# QO100_control.net
KiCad netlist of a schematic drawn in EAGLE
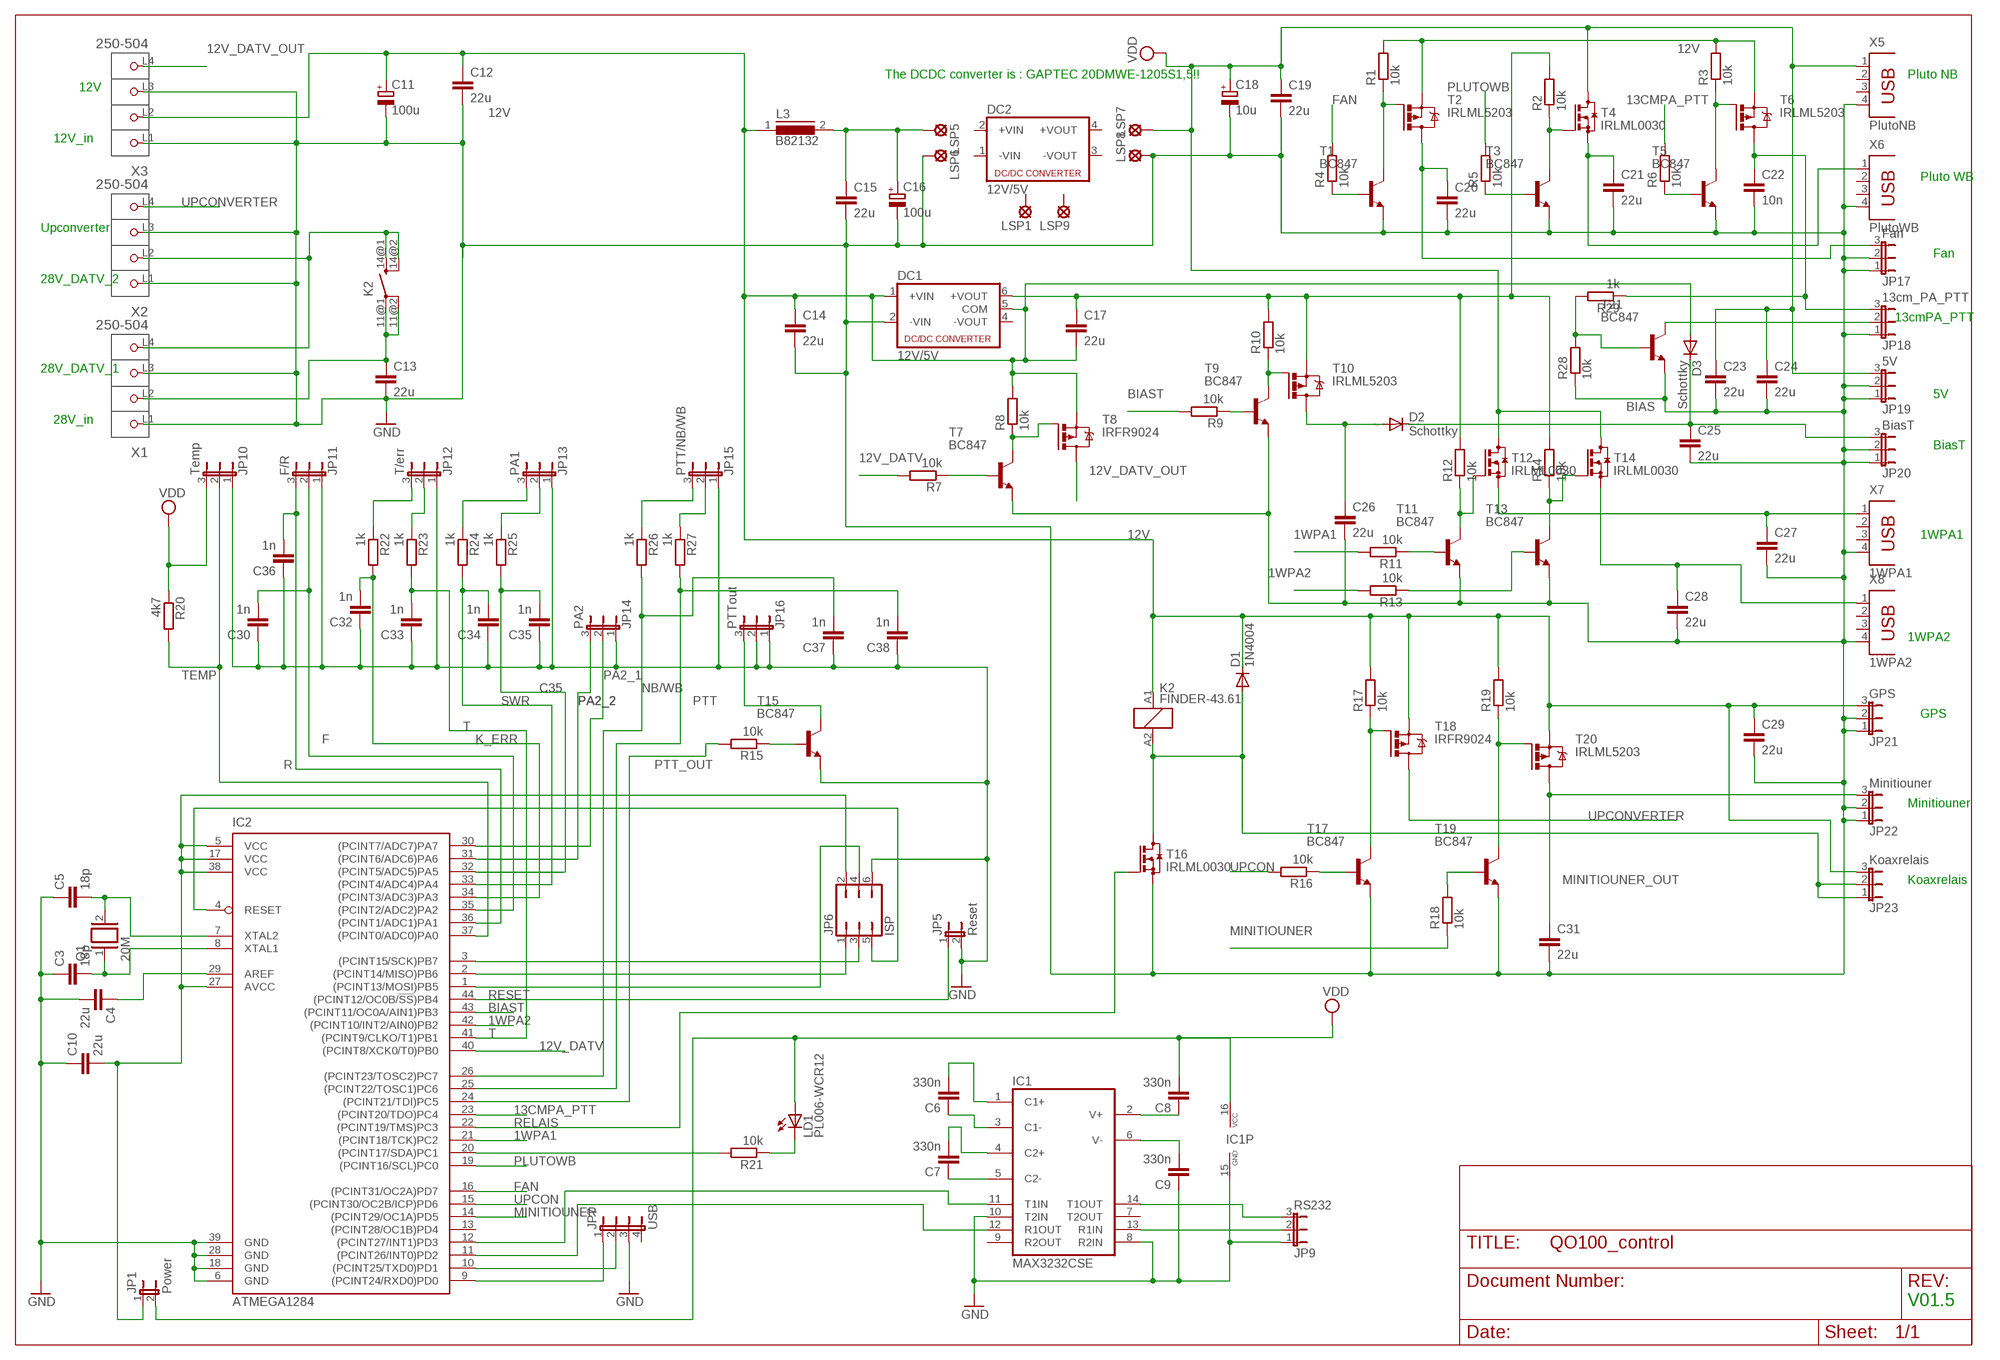
[diagram p0: schematic, sheet 1]

(export (version "E")
  (design (tool "Eeschema 10.0.6"))
  (components
    (comp (ref "C3")
      (value "18p")
      (footprint "eagle-import:C025-025X050")
      (libsource (lib "eagle-import") (part "C-EU025-025X050"))
    )
    (comp (ref "C4")
      (value "22u")
      (footprint "eagle-import:C1206")
      (libsource (lib "eagle-import") (part "resistor_C-EUC1206"))
    )
    (comp (ref "C5")
      (value "18p")
      (footprint "eagle-import:C025-025X050")
      (libsource (lib "eagle-import") (part "C-EU025-025X050"))
    )
    (comp (ref "C6")
      (value "330n")
      (footprint "eagle-import:C1206")
      (libsource (lib "eagle-import") (part "resistor_C-EUC1206"))
    )
    (comp (ref "C7")
      (value "330n")
      (footprint "eagle-import:C1206")
      (libsource (lib "eagle-import") (part "resistor_C-EUC1206"))
    )
    (comp (ref "C8")
      (value "330n")
      (footprint "eagle-import:C1206")
      (libsource (lib "eagle-import") (part "resistor_C-EUC1206"))
    )
    (comp (ref "C9")
      (value "330n")
      (footprint "eagle-import:C1206")
      (libsource (lib "eagle-import") (part "resistor_C-EUC1206"))
    )
    (comp (ref "C10")
      (value "22u")
      (footprint "eagle-import:C1206")
      (libsource (lib "eagle-import") (part "resistor_C-EUC1206"))
    )
    (comp (ref "C11")
      (value "100u")
      (footprint "eagle-import:E5-6")
      (libsource (lib "eagle-import") (part "CPOL-EUE5-6"))
    )
    (comp (ref "C12")
      (value "22u")
      (footprint "eagle-import:C1206")
      (libsource (lib "eagle-import") (part "resistor_C-EUC1206"))
    )
    (comp (ref "C13")
      (value "22u")
      (footprint "eagle-import:C1206")
      (libsource (lib "eagle-import") (part "resistor_C-EUC1206"))
    )
    (comp (ref "C14")
      (value "22u")
      (footprint "eagle-import:C1206")
      (libsource (lib "eagle-import") (part "resistor_C-EUC1206"))
    )
    (comp (ref "C15")
      (value "22u")
      (footprint "eagle-import:C1206")
      (libsource (lib "eagle-import") (part "resistor_C-EUC1206"))
    )
    (comp (ref "C16")
      (value "100u")
      (footprint "eagle-import:E5-6")
      (libsource (lib "eagle-import") (part "CPOL-EUE5-6"))
    )
    (comp (ref "C17")
      (value "22u")
      (footprint "eagle-import:C1206")
      (libsource (lib "eagle-import") (part "resistor_C-EUC1206"))
    )
    (comp (ref "C18")
      (value "10u")
      (footprint "eagle-import:E5-6")
      (libsource (lib "eagle-import") (part "CPOL-EUE5-6"))
    )
    (comp (ref "C19")
      (value "22u")
      (footprint "eagle-import:C1206")
      (libsource (lib "eagle-import") (part "resistor_C-EUC1206"))
    )
    (comp (ref "C20")
      (value "22u")
      (footprint "eagle-import:C1206")
      (libsource (lib "eagle-import") (part "resistor_C-EUC1206"))
    )
    (comp (ref "C21")
      (value "22u")
      (footprint "eagle-import:C1206")
      (libsource (lib "eagle-import") (part "resistor_C-EUC1206"))
    )
    (comp (ref "C22")
      (value "10n")
      (footprint "eagle-import:C1206")
      (libsource (lib "eagle-import") (part "resistor_C-EUC1206"))
    )
    (comp (ref "C23")
      (value "22u")
      (footprint "eagle-import:C1206")
      (libsource (lib "eagle-import") (part "resistor_C-EUC1206"))
    )
    (comp (ref "C24")
      (value "22u")
      (footprint "eagle-import:C1206")
      (libsource (lib "eagle-import") (part "resistor_C-EUC1206"))
    )
    (comp (ref "C25")
      (value "22u")
      (footprint "eagle-import:C1206")
      (libsource (lib "eagle-import") (part "resistor_C-EUC1206"))
    )
    (comp (ref "C26")
      (value "22u")
      (footprint "eagle-import:C1206")
      (libsource (lib "eagle-import") (part "resistor_C-EUC1206"))
    )
    (comp (ref "C27")
      (value "22u")
      (footprint "eagle-import:C1206")
      (libsource (lib "eagle-import") (part "resistor_C-EUC1206"))
    )
    (comp (ref "C28")
      (value "22u")
      (footprint "eagle-import:C1206")
      (libsource (lib "eagle-import") (part "resistor_C-EUC1206"))
    )
    (comp (ref "C29")
      (value "22u")
      (footprint "eagle-import:C1206")
      (libsource (lib "eagle-import") (part "resistor_C-EUC1206"))
    )
    (comp (ref "C30")
      (value "1n")
      (footprint "eagle-import:C1206")
      (libsource (lib "eagle-import") (part "resistor_C-EUC1206"))
    )
    (comp (ref "C31")
      (value "22u")
      (footprint "eagle-import:C1206")
      (libsource (lib "eagle-import") (part "resistor_C-EUC1206"))
    )
    (comp (ref "C32")
      (value "1n")
      (footprint "eagle-import:C1206")
      (libsource (lib "eagle-import") (part "resistor_C-EUC1206"))
    )
    (comp (ref "C33")
      (value "1n")
      (footprint "eagle-import:C1206")
      (libsource (lib "eagle-import") (part "resistor_C-EUC1206"))
    )
    (comp (ref "C34")
      (value "1n")
      (footprint "eagle-import:C1206")
      (libsource (lib "eagle-import") (part "resistor_C-EUC1206"))
    )
    (comp (ref "C35")
      (value "1n")
      (footprint "eagle-import:C1206")
      (libsource (lib "eagle-import") (part "resistor_C-EUC1206"))
    )
    (comp (ref "C36")
      (value "1n")
      (footprint "eagle-import:C1206")
      (libsource (lib "eagle-import") (part "resistor_C-EUC1206"))
    )
    (comp (ref "C37")
      (value "1n")
      (footprint "eagle-import:C1206")
      (libsource (lib "eagle-import") (part "resistor_C-EUC1206"))
    )
    (comp (ref "C38")
      (value "1n")
      (footprint "eagle-import:C1206")
      (libsource (lib "eagle-import") (part "resistor_C-EUC1206"))
    )
    (comp (ref "D1")
      (value "1N4004")
      (footprint "eagle-import:DO41-10")
      (libsource (lib "eagle-import") (part "1N4004"))
    )
    (comp (ref "D2")
      (value "Schottky")
      (footprint "eagle-import:DO41-10")
      (libsource (lib "eagle-import") (part "1N4004"))
    )
    (comp (ref "D3")
      (value "Schottky")
      (footprint "eagle-import:DO41-10")
      (libsource (lib "eagle-import") (part "1N4004"))
    )
    (comp (ref "DC1")
      (value "12V/5V")
      (footprint "eagle-import:NMA")
      (fields (field (name "MF") "C & D TECHNOLOGIES, INC") (field (name "MPN") "NMA0515SC"))
      (libsource (lib "eagle-import") (part "NMA"))
    )
    (comp (ref "DC2")
      (value "12V/5V")
      (footprint "eagle-import:NME")
      (fields (field (name "MF") "C & D TECHNOLOGIES, INC") (field (name "MPN") "NME1205D"))
      (libsource (lib "eagle-import") (part "NME"))
    )
    (comp (ref "IC1")
      (value "MAX3232CSE")
      (footprint "eagle-import:SO16")
      (libsource (lib "eagle-import") (part "MAX3232SEC"))
    )
    (comp (ref "IC2")
      (value "ATMEGA1284")
      (footprint "eagle-import:TQFP44")
      (fields (field (name "MPN") "ATMEGA644PV-10AU"))
      (libsource (lib "eagle-import") (part "ATMEGA644A"))
    )
    (comp (ref "JP1")
      (value "Power")
      (footprint "eagle-import:JP1")
      (libsource (lib "eagle-import") (part "JP1E"))
    )
    (comp (ref "JP5")
      (value "Reset")
      (footprint "eagle-import:JP1")
      (libsource (lib "eagle-import") (part "JP1E"))
    )
    (comp (ref "JP6")
      (value "ISP")
      (footprint "eagle-import:JP3Q")
      (libsource (lib "eagle-import") (part "JP3Q"))
    )
    (comp (ref "JP7")
      (value "USB")
      (footprint "eagle-import:JP4")
      (libsource (lib "eagle-import") (part "JP4E"))
    )
    (comp (ref "JP9")
      (value "RS232")
      (footprint "eagle-import:JP2")
      (libsource (lib "eagle-import") (part "JP2E"))
    )
    (comp (ref "JP10")
      (value "Temp")
      (footprint "eagle-import:JP2")
      (libsource (lib "eagle-import") (part "JP2E"))
    )
    (comp (ref "JP11")
      (value "F/R")
      (footprint "eagle-import:JP2")
      (libsource (lib "eagle-import") (part "JP2E"))
    )
    (comp (ref "JP12")
      (value "T/err")
      (footprint "eagle-import:JP2")
      (libsource (lib "eagle-import") (part "JP2E"))
    )
    (comp (ref "JP13")
      (value "PA1")
      (footprint "eagle-import:JP2")
      (libsource (lib "eagle-import") (part "JP2E"))
    )
    (comp (ref "JP14")
      (value "PA2")
      (footprint "eagle-import:JP2")
      (libsource (lib "eagle-import") (part "JP2E"))
    )
    (comp (ref "JP15")
      (value "PTT/NB/WB")
      (footprint "eagle-import:JP2")
      (libsource (lib "eagle-import") (part "JP2E"))
    )
    (comp (ref "JP16")
      (value "PTTout")
      (footprint "eagle-import:JP2")
      (libsource (lib "eagle-import") (part "JP2E"))
    )
    (comp (ref "JP17")
      (value "Fan")
      (footprint "eagle-import:JP2")
      (libsource (lib "eagle-import") (part "JP2E"))
    )
    (comp (ref "JP18")
      (value "13cm_PA_PTT")
      (footprint "eagle-import:JP2")
      (libsource (lib "eagle-import") (part "JP2E"))
    )
    (comp (ref "JP19")
      (value "5V")
      (footprint "eagle-import:JP2")
      (libsource (lib "eagle-import") (part "JP2E"))
    )
    (comp (ref "JP20")
      (value "BiasT")
      (footprint "eagle-import:JP2")
      (libsource (lib "eagle-import") (part "JP2E"))
    )
    (comp (ref "JP21")
      (value "GPS")
      (footprint "eagle-import:JP2")
      (libsource (lib "eagle-import") (part "JP2E"))
    )
    (comp (ref "JP22")
      (value "Minitiouner")
      (footprint "eagle-import:JP2")
      (libsource (lib "eagle-import") (part "JP2E"))
    )
    (comp (ref "JP23")
      (value "Koaxrelais")
      (footprint "eagle-import:JP2")
      (libsource (lib "eagle-import") (part "JP2E"))
    )
    (comp (ref "K2")
      (value "FINDER-43.61")
      (footprint "eagle-import:FINDER-43.61")
      (libsource (lib "eagle-import") (part "FINDER-43.61"))
    )
    (comp (ref "L3")
      (value "B82132")
      (footprint "eagle-import:SUKW2-22")
      (libsource (lib "eagle-import") (part "B82132"))
    )
    (comp (ref "LD1")
      (value "PL006-WCR12")
      (footprint "eagle-import:SOT23")
      (libsource (lib "eagle-import") (part "PL006-WCR12"))
    )
    (comp (ref "LSP1")
      (value "SE14")
      (footprint "eagle-import:SE14")
      (libsource (lib "eagle-import") (part "SE14"))
    )
    (comp (ref "LSP5")
      (value "SE14")
      (footprint "eagle-import:SE14")
      (libsource (lib "eagle-import") (part "SE14"))
    )
    (comp (ref "LSP6")
      (value "SE14")
      (footprint "eagle-import:SE14")
      (libsource (lib "eagle-import") (part "SE14"))
    )
    (comp (ref "LSP7")
      (value "SE14")
      (footprint "eagle-import:SE14")
      (libsource (lib "eagle-import") (part "SE14"))
    )
    (comp (ref "LSP8")
      (value "SE14")
      (footprint "eagle-import:SE14")
      (libsource (lib "eagle-import") (part "SE14"))
    )
    (comp (ref "LSP9")
      (value "SE14")
      (footprint "eagle-import:SE14")
      (libsource (lib "eagle-import") (part "SE14"))
    )
    (comp (ref "Q1")
      (value "20M")
      (footprint "eagle-import:QS")
      (libsource (lib "eagle-import") (part "XTAL/S"))
    )
    (comp (ref "R1")
      (value "10k")
      (footprint "eagle-import:R1206")
      (libsource (lib "eagle-import") (part "R-EU_R1206"))
    )
    (comp (ref "R2")
      (value "10k")
      (footprint "eagle-import:R1206")
      (libsource (lib "eagle-import") (part "R-EU_R1206"))
    )
    (comp (ref "R3")
      (value "10k")
      (footprint "eagle-import:R1206")
      (libsource (lib "eagle-import") (part "R-EU_R1206"))
    )
    (comp (ref "R4")
      (value "10k")
      (footprint "eagle-import:R1206")
      (libsource (lib "eagle-import") (part "R-EU_R1206"))
    )
    (comp (ref "R5")
      (value "10k")
      (footprint "eagle-import:R1206")
      (libsource (lib "eagle-import") (part "R-EU_R1206"))
    )
    (comp (ref "R6")
      (value "10k")
      (footprint "eagle-import:R1206")
      (libsource (lib "eagle-import") (part "R-EU_R1206"))
    )
    (comp (ref "R7")
      (value "10k")
      (footprint "eagle-import:R1206")
      (libsource (lib "eagle-import") (part "R-EU_R1206"))
    )
    (comp (ref "R8")
      (value "10k")
      (footprint "eagle-import:R1206")
      (libsource (lib "eagle-import") (part "R-EU_R1206"))
    )
    (comp (ref "R9")
      (value "10k")
      (footprint "eagle-import:R1206")
      (libsource (lib "eagle-import") (part "R-EU_R1206"))
    )
    (comp (ref "R10")
      (value "10k")
      (footprint "eagle-import:R1206")
      (libsource (lib "eagle-import") (part "R-EU_R1206"))
    )
    (comp (ref "R11")
      (value "10k")
      (footprint "eagle-import:R1206")
      (libsource (lib "eagle-import") (part "R-EU_R1206"))
    )
    (comp (ref "R12")
      (value "10k")
      (footprint "eagle-import:R1206")
      (libsource (lib "eagle-import") (part "R-EU_R1206"))
    )
    (comp (ref "R13")
      (value "10k")
      (footprint "eagle-import:R1206")
      (libsource (lib "eagle-import") (part "R-EU_R1206"))
    )
    (comp (ref "R14")
      (value "10k")
      (footprint "eagle-import:R1206")
      (libsource (lib "eagle-import") (part "R-EU_R1206"))
    )
    (comp (ref "R15")
      (value "10k")
      (footprint "eagle-import:R1206")
      (libsource (lib "eagle-import") (part "R-EU_R1206"))
    )
    (comp (ref "R16")
      (value "10k")
      (footprint "eagle-import:R1206")
      (libsource (lib "eagle-import") (part "R-EU_R1206"))
    )
    (comp (ref "R17")
      (value "10k")
      (footprint "eagle-import:R1206")
      (libsource (lib "eagle-import") (part "R-EU_R1206"))
    )
    (comp (ref "R18")
      (value "10k")
      (footprint "eagle-import:R1206")
      (libsource (lib "eagle-import") (part "R-EU_R1206"))
    )
    (comp (ref "R19")
      (value "10k")
      (footprint "eagle-import:R1206")
      (libsource (lib "eagle-import") (part "R-EU_R1206"))
    )
    (comp (ref "R20")
      (value "4k7")
      (footprint "eagle-import:R1206")
      (libsource (lib "eagle-import") (part "R-EU_R1206"))
    )
    (comp (ref "R21")
      (value "10k")
      (footprint "eagle-import:R1206")
      (libsource (lib "eagle-import") (part "R-EU_R1206"))
    )
    (comp (ref "R22")
      (value "1k")
      (footprint "eagle-import:R1206")
      (libsource (lib "eagle-import") (part "R-EU_R1206"))
    )
    (comp (ref "R23")
      (value "1k")
      (footprint "eagle-import:R1206")
      (libsource (lib "eagle-import") (part "R-EU_R1206"))
    )
    (comp (ref "R24")
      (value "1k")
      (footprint "eagle-import:R1206")
      (libsource (lib "eagle-import") (part "R-EU_R1206"))
    )
    (comp (ref "R25")
      (value "1k")
      (footprint "eagle-import:R1206")
      (libsource (lib "eagle-import") (part "R-EU_R1206"))
    )
    (comp (ref "R26")
      (value "1k")
      (footprint "eagle-import:R1206")
      (libsource (lib "eagle-import") (part "R-EU_R1206"))
    )
    (comp (ref "R27")
      (value "1k")
      (footprint "eagle-import:R1206")
      (libsource (lib "eagle-import") (part "R-EU_R1206"))
    )
    (comp (ref "R28")
      (value "10k")
      (footprint "eagle-import:R1206")
      (libsource (lib "eagle-import") (part "R-EU_R1206"))
    )
    (comp (ref "R29")
      (value "1k")
      (footprint "eagle-import:R1206")
      (libsource (lib "eagle-import") (part "R-EU_R1206"))
    )
    (comp (ref "T1")
      (value "BC847")
      (footprint "eagle-import:SOT23")
      (libsource (lib "eagle-import") (part "BC847"))
    )
    (comp (ref "T2")
      (value "IRLML5203")
      (footprint "eagle-import:MICRO3")
      (libsource (lib "eagle-import") (part "IRLML5203"))
    )
    (comp (ref "T3")
      (value "BC847")
      (footprint "eagle-import:SOT23")
      (libsource (lib "eagle-import") (part "BC847"))
    )
    (comp (ref "T4")
      (value "IRLML0030")
      (footprint "eagle-import:SOT23")
      (libsource (lib "eagle-import") (part "BSS123"))
    )
    (comp (ref "T5")
      (value "BC847")
      (footprint "eagle-import:SOT23")
      (libsource (lib "eagle-import") (part "BC847"))
    )
    (comp (ref "T6")
      (value "IRLML5203")
      (footprint "eagle-import:MICRO3")
      (libsource (lib "eagle-import") (part "IRLML5203"))
    )
    (comp (ref "T7")
      (value "BC847")
      (footprint "eagle-import:SOT23")
      (libsource (lib "eagle-import") (part "BC847"))
    )
    (comp (ref "T8")
      (value "IRFR9024")
      (footprint "eagle-import:D-PAK_TO252AA")
      (libsource (lib "eagle-import") (part "IRF?5305R"))
    )
    (comp (ref "T9")
      (value "BC847")
      (footprint "eagle-import:SOT23")
      (libsource (lib "eagle-import") (part "BC847"))
    )
    (comp (ref "T10")
      (value "IRLML5203")
      (footprint "eagle-import:MICRO3")
      (libsource (lib "eagle-import") (part "IRLML5203"))
    )
    (comp (ref "T11")
      (value "BC847")
      (footprint "eagle-import:SOT23")
      (libsource (lib "eagle-import") (part "BC847"))
    )
    (comp (ref "T12")
      (value "IRLML0030")
      (footprint "eagle-import:SOT23")
      (libsource (lib "eagle-import") (part "BSS123"))
    )
    (comp (ref "T13")
      (value "BC847")
      (footprint "eagle-import:SOT23")
      (libsource (lib "eagle-import") (part "BC847"))
    )
    (comp (ref "T14")
      (value "IRLML0030")
      (footprint "eagle-import:SOT23")
      (libsource (lib "eagle-import") (part "BSS123"))
    )
    (comp (ref "T15")
      (value "BC847")
      (footprint "eagle-import:SOT23")
      (libsource (lib "eagle-import") (part "BC847"))
    )
    (comp (ref "T16")
      (value "IRLML0030")
      (footprint "eagle-import:SOT23")
      (libsource (lib "eagle-import") (part "BSS123"))
    )
    (comp (ref "T17")
      (value "BC847")
      (footprint "eagle-import:SOT23")
      (libsource (lib "eagle-import") (part "BC847"))
    )
    (comp (ref "T18")
      (value "IRFR9024")
      (footprint "eagle-import:D-PAK_TO252AA")
      (libsource (lib "eagle-import") (part "IRF?5305R"))
    )
    (comp (ref "T19")
      (value "BC847")
      (footprint "eagle-import:SOT23")
      (libsource (lib "eagle-import") (part "BC847"))
    )
    (comp (ref "T20")
      (value "IRLML5203")
      (footprint "eagle-import:MICRO3")
      (libsource (lib "eagle-import") (part "IRLML5203"))
    )
    (comp (ref "T21")
      (value "BC847")
      (footprint "eagle-import:SOT23")
      (libsource (lib "eagle-import") (part "BC847"))
    )
    (comp (ref "X1")
      (value "250-504")
      (footprint "eagle-import:P-250-504")
      (fields (field (name "MF") "WAGO"))
      (libsource (lib "eagle-import") (part "250-504"))
    )
    (comp (ref "X2")
      (value "250-504")
      (footprint "eagle-import:P-250-504")
      (fields (field (name "MF") "WAGO"))
      (libsource (lib "eagle-import") (part "250-504"))
    )
    (comp (ref "X3")
      (value "250-504")
      (footprint "eagle-import:P-250-504")
      (fields (field (name "MF") "WAGO"))
      (libsource (lib "eagle-import") (part "250-504"))
    )
    (comp (ref "X5")
      (value "PlutoNB")
      (footprint "eagle-import:PN87520")
      (libsource (lib "eagle-import") (part "PN87520"))
    )
    (comp (ref "X6")
      (value "PlutoWB")
      (footprint "eagle-import:PN87520")
      (libsource (lib "eagle-import") (part "PN87520"))
    )
    (comp (ref "X7")
      (value "1WPA1")
      (footprint "eagle-import:PN87520")
      (libsource (lib "eagle-import") (part "PN87520"))
    )
    (comp (ref "X8")
      (value "1WPA2")
      (footprint "eagle-import:PN87520")
      (libsource (lib "eagle-import") (part "PN87520"))
    )
  )
  (nets
    (net (code "1") (name "/1WPA1") (class "Default")
      (node (ref "IC2") (pin "21") (pinfunction "(PCINT18/TCK)PC2_21") (pintype "output"))
      (node (ref "R11") (pin "2") (pinfunction "2_2") (pintype "passive"))
    )
    (net (code "2") (name "/1WPA2") (class "Default")
      (node (ref "IC2") (pin "42") (pinfunction "(PCINT10/INT2/AIN0)PB2_42") (pintype "bidirectional"))
      (node (ref "R13") (pin "2") (pinfunction "2_2") (pintype "passive"))
    )
    (net (code "3") (name "/12V") (class "Default")
      (node (ref "C11") (pin "+") (pinfunction "+_+") (pintype "passive"))
      (node (ref "C12") (pin "1") (pinfunction "1_1") (pintype "passive"))
      (node (ref "C14") (pin "1") (pinfunction "1_1") (pintype "passive"))
      (node (ref "C17") (pin "2") (pinfunction "2_2") (pintype "passive"))
      (node (ref "C29") (pin "1") (pinfunction "1_1") (pintype "passive"))
      (node (ref "D1") (pin "C") (pinfunction "C_C") (pintype "passive"))
      (node (ref "D3") (pin "A") (pinfunction "A_A") (pintype "passive"))
      (node (ref "DC1") (pin "1") (pinfunction "+VIN_1") (pintype "passive"))
      (node (ref "DC1") (pin "5") (pinfunction "COM_5") (pintype "passive"))
      (node (ref "JP21") (pin "3") (pinfunction "3_3") (pintype "passive"))
      (node (ref "JP23") (pin "3") (pinfunction "3_3") (pintype "passive"))
      (node (ref "K2") (pin "A1") (pinfunction "1_A1") (pintype "passive"))
      (node (ref "L3") (pin "1") (pinfunction "1_1") (pintype "passive"))
      (node (ref "R1") (pin "2") (pinfunction "2_2") (pintype "passive"))
      (node (ref "R17") (pin "2") (pinfunction "2_2") (pintype "passive"))
      (node (ref "R19") (pin "2") (pinfunction "2_2") (pintype "passive"))
      (node (ref "R3") (pin "2") (pinfunction "2_2") (pintype "passive"))
      (node (ref "R8") (pin "2") (pinfunction "2_2") (pintype "passive"))
      (node (ref "T18") (pin "3") (pinfunction "S_3") (pintype "passive"))
      (node (ref "T2") (pin "2") (pinfunction "S_2") (pintype "passive"))
      (node (ref "T20") (pin "2") (pinfunction "S_2") (pintype "passive"))
      (node (ref "T6") (pin "2") (pinfunction "S_2") (pintype "passive"))
      (node (ref "T8") (pin "3") (pinfunction "S_3") (pintype "passive"))
      (node (ref "X3") (pin "L2") (pinfunction "P2_L2") (pintype "bidirectional"))
    )
    (net (code "4") (name "/12V_DATV") (class "Default")
      (node (ref "IC2") (pin "40") (pinfunction "(PCINT8/XCK0/T0)PB0_40") (pintype "bidirectional"))
      (node (ref "R7") (pin "2") (pinfunction "2_2") (pintype "passive"))
    )
    (net (code "5") (name "/12V_DATV_OUT") (class "Default")
      (node (ref "T8") (pin "4") (pinfunction "D_4") (pintype "passive"))
      (node (ref "X3") (pin "L4") (pinfunction "P4_L4") (pintype "bidirectional"))
    )
    (net (code "6") (name "/13CMPA_PTT") (class "Default")
      (node (ref "IC2") (pin "23") (pinfunction "(PCINT20/TDO)PC4_23") (pintype "output"))
      (node (ref "R6") (pin "2") (pinfunction "2_2") (pintype "passive"))
    )
    (net (code "7") (name "/BIAS") (class "Default")
      (node (ref "C25") (pin "1") (pinfunction "1_1") (pintype "passive"))
      (node (ref "D2") (pin "C") (pinfunction "C_C") (pintype "passive"))
      (node (ref "D3") (pin "C") (pinfunction "C_C") (pintype "passive"))
      (node (ref "JP20") (pin "3") (pinfunction "3_3") (pintype "passive"))
    )
    (net (code "8") (name "/BIAST") (class "Default")
      (node (ref "IC2") (pin "43") (pinfunction "(PCINT11/OC0A/AIN1)PB3_43") (pintype "bidirectional"))
      (node (ref "R9") (pin "2") (pinfunction "2_2") (pintype "passive"))
    )
    (net (code "9") (name "/C35") (class "Default")
      (node (ref "C35") (pin "2") (pinfunction "2_2") (pintype "passive"))
      (node (ref "IC2") (pin "32") (pinfunction "(PCINT5/ADC5)PA5_32") (pintype "bidirectional"))
      (node (ref "R25") (pin "2") (pinfunction "2_2") (pintype "passive"))
    )
    (net (code "10") (name "/F") (class "Default")
      (node (ref "C30") (pin "2") (pinfunction "2_2") (pintype "passive"))
      (node (ref "IC2") (pin "35") (pinfunction "(PCINT2/ADC2)PA2_35") (pintype "bidirectional"))
      (node (ref "JP11") (pin "2") (pinfunction "2_2") (pintype "passive"))
    )
    (net (code "11") (name "/FAN") (class "Default")
      (node (ref "IC2") (pin "16") (pinfunction "(PCINT31/OC2A)PD7_16") (pintype "bidirectional"))
      (node (ref "R4") (pin "2") (pinfunction "2_2") (pintype "passive"))
    )
    (net (code "12") (name "/K_ERR") (class "Default")
      (node (ref "C32") (pin "2") (pinfunction "2_2") (pintype "passive"))
      (node (ref "IC2") (pin "34") (pinfunction "(PCINT3/ADC3)PA3_34") (pintype "bidirectional"))
      (node (ref "R22") (pin "2") (pinfunction "2_2") (pintype "passive"))
    )
    (net (code "13") (name "/MINITIOUNER") (class "Default")
      (node (ref "IC2") (pin "14") (pinfunction "(PCINT29/OC1A)PD5_14") (pintype "bidirectional"))
      (node (ref "R18") (pin "1") (pinfunction "1_1") (pintype "passive"))
    )
    (net (code "14") (name "/MINITIOUNER_OUT") (class "Default")
      (node (ref "C31") (pin "1") (pinfunction "1_1") (pintype "passive"))
      (node (ref "JP22") (pin "3") (pinfunction "3_3") (pintype "passive"))
      (node (ref "T20") (pin "3") (pinfunction "D_3") (pintype "passive"))
    )
    (net (code "15") (name "/NB{slash}WB") (class "Default")
      (node (ref "C37") (pin "2") (pinfunction "2_2") (pintype "passive"))
      (node (ref "IC2") (pin "26") (pinfunction "(PCINT23/TOSC2)PC7_26") (pintype "output"))
      (node (ref "R26") (pin "2") (pinfunction "2_2") (pintype "passive"))
    )
    (net (code "16") (name "/PA2_1") (class "Default")
      (node (ref "IC2") (pin "30") (pinfunction "(PCINT7/ADC7)PA7_30") (pintype "bidirectional"))
      (node (ref "JP14") (pin "2") (pinfunction "2_2") (pintype "passive"))
    )
    (net (code "17") (name "/PA2_2") (class "Default")
      (node (ref "IC2") (pin "31") (pinfunction "(PCINT6/ADC6)PA6_31") (pintype "bidirectional"))
      (node (ref "JP14") (pin "3") (pinfunction "3_3") (pintype "passive"))
    )
    (net (code "18") (name "/PLUTOWB") (class "Default")
      (node (ref "IC2") (pin "19") (pinfunction "(PCINT16/SCL)PC0_19") (pintype "output"))
      (node (ref "R5") (pin "2") (pinfunction "2_2") (pintype "passive"))
    )
    (net (code "19") (name "/PTT") (class "Default")
      (node (ref "C38") (pin "2") (pinfunction "2_2") (pintype "passive"))
      (node (ref "IC2") (pin "25") (pinfunction "(PCINT22/TOSC1)PC6_25") (pintype "output"))
      (node (ref "R27") (pin "2") (pinfunction "2_2") (pintype "passive"))
    )
    (net (code "20") (name "/PTT_OUT") (class "Default")
      (node (ref "IC2") (pin "24") (pinfunction "(PCINT21/TDI)PC5_24") (pintype "output"))
      (node (ref "R15") (pin "2") (pinfunction "2_2") (pintype "passive"))
    )
    (net (code "21") (name "/R") (class "Default")
      (node (ref "C36") (pin "2") (pinfunction "2_2") (pintype "passive"))
      (node (ref "IC2") (pin "36") (pinfunction "(PCINT1/ADC1)PA1_36") (pintype "bidirectional"))
      (node (ref "JP11") (pin "3") (pinfunction "3_3") (pintype "passive"))
    )
    (net (code "22") (name "/RELAIS") (class "Default")
      (node (ref "IC2") (pin "22") (pinfunction "(PCINT19/TMS)PC3_22") (pintype "output"))
      (node (ref "T16") (pin "1") (pinfunction "G_1") (pintype "passive"))
    )
    (net (code "23") (name "/RESET") (class "Default")
      (node (ref "IC2") (pin "44") (pinfunction "(PCINT12/OC0B/~{SS})PB4_44") (pintype "bidirectional"))
      (node (ref "JP5") (pin "1") (pinfunction "1_1") (pintype "passive"))
    )
    (net (code "24") (name "/SWR") (class "Default")
      (node (ref "C34") (pin "2") (pinfunction "2_2") (pintype "passive"))
      (node (ref "IC2") (pin "33") (pinfunction "(PCINT4/ADC4)PA4_33") (pintype "bidirectional"))
      (node (ref "R24") (pin "2") (pinfunction "2_2") (pintype "passive"))
    )
    (net (code "25") (name "/T") (class "Default")
      (node (ref "C33") (pin "2") (pinfunction "2_2") (pintype "passive"))
      (node (ref "IC2") (pin "41") (pinfunction "(PCINT9/CLKO/T1)PB1_41") (pintype "bidirectional"))
      (node (ref "R23") (pin "2") (pinfunction "2_2") (pintype "passive"))
    )
    (net (code "26") (name "/TEMP") (class "Default")
      (node (ref "IC2") (pin "37") (pinfunction "(PCINT0/ADC0)PA0_37") (pintype "bidirectional"))
      (node (ref "JP10") (pin "2") (pinfunction "2_2") (pintype "passive"))
      (node (ref "R20") (pin "2") (pinfunction "2_2") (pintype "passive"))
    )
    (net (code "27") (name "/UPCON") (class "Default")
      (node (ref "IC2") (pin "15") (pinfunction "(PCINT30/OC2B/ICP)PD6_15") (pintype "bidirectional"))
      (node (ref "R16") (pin "2") (pinfunction "2_2") (pintype "passive"))
    )
    (net (code "28") (name "/UPCONVERTER") (class "Default")
      (node (ref "T18") (pin "4") (pinfunction "D_4") (pintype "passive"))
      (node (ref "X2") (pin "L4") (pinfunction "P4_L4") (pintype "bidirectional"))
    )
    (net (code "29") (name "GND") (class "Default")
      (node (ref "C10") (pin "1") (pinfunction "1_1") (pintype "passive"))
      (node (ref "C11") (pin "-") (pinfunction "-_-") (pintype "passive"))
      (node (ref "C12") (pin "2") (pinfunction "2_2") (pintype "passive"))
      (node (ref "C13") (pin "2") (pinfunction "2_2") (pintype "passive"))
      (node (ref "C14") (pin "2") (pinfunction "2_2") (pintype "passive"))
      (node (ref "C15") (pin "2") (pinfunction "2_2") (pintype "passive"))
      (node (ref "C16") (pin "-") (pinfunction "-_-") (pintype "passive"))
      (node (ref "C18") (pin "-") (pinfunction "-_-") (pintype "passive"))
      (node (ref "C19") (pin "2") (pinfunction "2_2") (pintype "passive"))
      (node (ref "C20") (pin "2") (pinfunction "2_2") (pintype "passive"))
      (node (ref "C21") (pin "2") (pinfunction "2_2") (pintype "passive"))
      (node (ref "C22") (pin "2") (pinfunction "2_2") (pintype "passive"))
      (node (ref "C23") (pin "2") (pinfunction "2_2") (pintype "passive"))
      (node (ref "C24") (pin "2") (pinfunction "2_2") (pintype "passive"))
      (node (ref "C25") (pin "2") (pinfunction "2_2") (pintype "passive"))
      (node (ref "C26") (pin "2") (pinfunction "2_2") (pintype "passive"))
      (node (ref "C27") (pin "2") (pinfunction "2_2") (pintype "passive"))
      (node (ref "C28") (pin "2") (pinfunction "2_2") (pintype "passive"))
      (node (ref "C29") (pin "2") (pinfunction "2_2") (pintype "passive"))
      (node (ref "C3") (pin "1") (pinfunction "1_1") (pintype "passive"))
      (node (ref "C30") (pin "1") (pinfunction "1_1") (pintype "passive"))
      (node (ref "C31") (pin "2") (pinfunction "2_2") (pintype "passive"))
      (node (ref "C32") (pin "1") (pinfunction "1_1") (pintype "passive"))
      (node (ref "C33") (pin "1") (pinfunction "1_1") (pintype "passive"))
      (node (ref "C34") (pin "1") (pinfunction "1_1") (pintype "passive"))
      (node (ref "C35") (pin "1") (pinfunction "1_1") (pintype "passive"))
      (node (ref "C36") (pin "1") (pinfunction "1_1") (pintype "passive"))
      (node (ref "C37") (pin "1") (pinfunction "1_1") (pintype "passive"))
      (node (ref "C38") (pin "1") (pinfunction "1_1") (pintype "passive"))
      (node (ref "C4") (pin "2") (pinfunction "2_2") (pintype "passive"))
      (node (ref "C5") (pin "1") (pinfunction "1_1") (pintype "passive"))
      (node (ref "C9") (pin "1") (pinfunction "1_1") (pintype "passive"))
      (node (ref "DC1") (pin "2") (pinfunction "-VIN_2") (pintype "passive"))
      (node (ref "IC1") (pin "10") (pinfunction "T2IN_10") (pintype "input"))
      (node (ref "IC1") (pin "15") (pinfunction "GND_15") (pintype "power_in"))
      (node (ref "IC1") (pin "8") (pinfunction "R2IN_8") (pintype "input"))
      (node (ref "IC2") (pin "18") (pinfunction "GND_18") (pintype "power_in"))
      (node (ref "IC2") (pin "28") (pinfunction "GND_28") (pintype "power_in"))
      (node (ref "IC2") (pin "39") (pinfunction "GND_39") (pintype "power_in"))
      (node (ref "IC2") (pin "6") (pinfunction "GND_6") (pintype "power_in"))
      (node (ref "JP10") (pin "1") (pinfunction "1_1") (pintype "passive"))
      (node (ref "JP11") (pin "1") (pinfunction "1_1") (pintype "passive"))
      (node (ref "JP12") (pin "1") (pinfunction "1_1") (pintype "passive"))
      (node (ref "JP13") (pin "1") (pinfunction "1_1") (pintype "passive"))
      (node (ref "JP14") (pin "1") (pinfunction "1_1") (pintype "passive"))
      (node (ref "JP15") (pin "1") (pinfunction "1_1") (pintype "passive"))
      (node (ref "JP16") (pin "1") (pinfunction "1_1") (pintype "passive"))
      (node (ref "JP16") (pin "2") (pinfunction "2_2") (pintype "passive"))
      (node (ref "JP17") (pin "1") (pinfunction "1_1") (pintype "passive"))
      (node (ref "JP17") (pin "2") (pinfunction "2_2") (pintype "passive"))
      (node (ref "JP18") (pin "1") (pinfunction "1_1") (pintype "passive"))
      (node (ref "JP19") (pin "1") (pinfunction "1_1") (pintype "passive"))
      (node (ref "JP19") (pin "2") (pinfunction "2_2") (pintype "passive"))
      (node (ref "JP20") (pin "1") (pinfunction "1_1") (pintype "passive"))
      (node (ref "JP20") (pin "2") (pinfunction "2_2") (pintype "passive"))
      (node (ref "JP21") (pin "1") (pinfunction "1_1") (pintype "passive"))
      (node (ref "JP21") (pin "2") (pinfunction "2_2") (pintype "passive"))
      (node (ref "JP22") (pin "1") (pinfunction "1_1") (pintype "passive"))
      (node (ref "JP22") (pin "2") (pinfunction "2_2") (pintype "passive"))
      (node (ref "JP5") (pin "2") (pinfunction "2_2") (pintype "passive"))
      (node (ref "JP6") (pin "6") (pinfunction "6_6") (pintype "passive"))
      (node (ref "JP7") (pin "3") (pinfunction "3_3") (pintype "passive"))
      (node (ref "JP9") (pin "1") (pinfunction "1_1") (pintype "passive"))
      (node (ref "LSP6") (pin "MP") (pinfunction "MP_MP") (pintype "passive"))
      (node (ref "LSP8") (pin "MP") (pinfunction "MP_MP") (pintype "passive"))
      (node (ref "R28") (pin "1") (pinfunction "1_1") (pintype "passive"))
      (node (ref "T1") (pin "2") (pinfunction "E_2") (pintype "passive"))
      (node (ref "T11") (pin "2") (pinfunction "E_2") (pintype "passive"))
      (node (ref "T13") (pin "2") (pinfunction "E_2") (pintype "passive"))
      (node (ref "T15") (pin "2") (pinfunction "E_2") (pintype "passive"))
      (node (ref "T16") (pin "2") (pinfunction "S_2") (pintype "passive"))
      (node (ref "T17") (pin "2") (pinfunction "E_2") (pintype "passive"))
      (node (ref "T19") (pin "2") (pinfunction "E_2") (pintype "passive"))
      (node (ref "T21") (pin "2") (pinfunction "E_2") (pintype "passive"))
      (node (ref "T3") (pin "2") (pinfunction "E_2") (pintype "passive"))
      (node (ref "T5") (pin "2") (pinfunction "E_2") (pintype "passive"))
      (node (ref "T7") (pin "2") (pinfunction "E_2") (pintype "passive"))
      (node (ref "T9") (pin "2") (pinfunction "E_2") (pintype "passive"))
      (node (ref "X1") (pin "L1") (pinfunction "P1_L1") (pintype "bidirectional"))
      (node (ref "X1") (pin "L3") (pinfunction "P3_L3") (pintype "bidirectional"))
      (node (ref "X2") (pin "L1") (pinfunction "P1_L1") (pintype "bidirectional"))
      (node (ref "X2") (pin "L3") (pinfunction "P3_L3") (pintype "bidirectional"))
      (node (ref "X3") (pin "L1") (pinfunction "P1_L1") (pintype "bidirectional"))
      (node (ref "X3") (pin "L3") (pinfunction "P3_L3") (pintype "bidirectional"))
      (node (ref "X5") (pin "4") (pinfunction "4_4") (pintype "passive"))
      (node (ref "X6") (pin "4") (pinfunction "4_4") (pintype "passive"))
      (node (ref "X7") (pin "4") (pinfunction "4_4") (pintype "passive"))
      (node (ref "X8") (pin "4") (pinfunction "4_4") (pintype "passive"))
    )
    (net (code "30") (name "Net-(C15-Pad1)") (class "Default")
      (node (ref "C15") (pin "1") (pinfunction "1_1") (pintype "passive"))
      (node (ref "C16") (pin "+") (pinfunction "+_+") (pintype "passive"))
      (node (ref "L3") (pin "2") (pinfunction "2_2") (pintype "passive"))
      (node (ref "LSP5") (pin "MP") (pinfunction "MP_MP") (pintype "passive"))
    )
    (net (code "31") (name "Net-(DC1-+VOUT)") (class "Default")
      (node (ref "C17") (pin "1") (pinfunction "1_1") (pintype "passive"))
      (node (ref "DC1") (pin "6") (pinfunction "+VOUT_6") (pintype "passive"))
      (node (ref "R10") (pin "2") (pinfunction "2_2") (pintype "passive"))
      (node (ref "R12") (pin "2") (pinfunction "2_2") (pintype "passive"))
      (node (ref "R14") (pin "2") (pinfunction "2_2") (pintype "passive"))
      (node (ref "R2") (pin "2") (pinfunction "2_2") (pintype "passive"))
      (node (ref "T10") (pin "2") (pinfunction "S_2") (pintype "passive"))
    )
    (net (code "32") (name "Net-(IC1A-C1+)") (class "Default")
      (node (ref "C6") (pin "2") (pinfunction "2_2") (pintype "passive"))
      (node (ref "IC1") (pin "1") (pinfunction "C1+_1") (pintype "bidirectional"))
    )
    (net (code "33") (name "Net-(IC1A-C1-)") (class "Default")
      (node (ref "C6") (pin "1") (pinfunction "1_1") (pintype "passive"))
      (node (ref "IC1") (pin "3") (pinfunction "C1-_3") (pintype "bidirectional"))
    )
    (net (code "34") (name "Net-(IC1A-C2+)") (class "Default")
      (node (ref "C7") (pin "2") (pinfunction "2_2") (pintype "passive"))
      (node (ref "IC1") (pin "4") (pinfunction "C2+_4") (pintype "bidirectional"))
    )
    (net (code "35") (name "Net-(IC1A-C2-)") (class "Default")
      (node (ref "C7") (pin "1") (pinfunction "1_1") (pintype "passive"))
      (node (ref "IC1") (pin "5") (pinfunction "C2-_5") (pintype "bidirectional"))
    )
    (net (code "36") (name "Net-(IC1A-R1IN)") (class "Default")
      (node (ref "IC1") (pin "13") (pinfunction "R1IN_13") (pintype "input"))
      (node (ref "JP9") (pin "2") (pinfunction "2_2") (pintype "passive"))
    )
    (net (code "37") (name "Net-(IC1A-R1OUT)") (class "Default")
      (node (ref "IC1") (pin "12") (pinfunction "R1OUT_12") (pintype "output"))
      (node (ref "IC2") (pin "11") (pinfunction "(PCINT26/INT0)PD2_11") (pintype "bidirectional"))
    )
    (net (code "38") (name "Net-(IC1A-T1IN)") (class "Default")
      (node (ref "IC1") (pin "11") (pinfunction "T1IN_11") (pintype "input"))
      (node (ref "IC2") (pin "12") (pinfunction "(PCINT27/INT1)PD3_12") (pintype "bidirectional"))
    )
    (net (code "39") (name "Net-(IC1A-T1OUT)") (class "Default")
      (node (ref "IC1") (pin "14") (pinfunction "T1OUT_14") (pintype "output"))
      (node (ref "JP9") (pin "3") (pinfunction "3_3") (pintype "passive"))
    )
    (net (code "40") (name "Net-(IC1A-V+)") (class "Default")
      (node (ref "C8") (pin "1") (pinfunction "1_1") (pintype "passive"))
      (node (ref "IC1") (pin "2") (pinfunction "V+_2") (pintype "bidirectional"))
    )
    (net (code "41") (name "Net-(IC1A-V-)") (class "Default")
      (node (ref "C9") (pin "2") (pinfunction "2_2") (pintype "passive"))
      (node (ref "IC1") (pin "6") (pinfunction "V-_6") (pintype "bidirectional"))
    )
    (net (code "42") (name "Net-(IC2-(PCINT13{slash}MOSI)PB5)") (class "Default")
      (node (ref "IC2") (pin "1") (pinfunction "(PCINT13/MOSI)PB5_1") (pintype "bidirectional"))
      (node (ref "JP6") (pin "4") (pinfunction "4_4") (pintype "passive"))
    )
    (net (code "43") (name "Net-(IC2-(PCINT14{slash}MISO)PB6)") (class "Default")
      (node (ref "IC2") (pin "2") (pinfunction "(PCINT14/MISO)PB6_2") (pintype "bidirectional"))
      (node (ref "JP6") (pin "1") (pinfunction "1_1") (pintype "passive"))
    )
    (net (code "44") (name "Net-(IC2-(PCINT15{slash}SCK)PB7)") (class "Default")
      (node (ref "IC2") (pin "3") (pinfunction "(PCINT15/SCK)PB7_3") (pintype "bidirectional"))
      (node (ref "JP6") (pin "3") (pinfunction "3_3") (pintype "passive"))
    )
    (net (code "45") (name "Net-(IC2-(PCINT17{slash}SDA)PC1)") (class "Default")
      (node (ref "IC2") (pin "20") (pinfunction "(PCINT17/SDA)PC1_20") (pintype "output"))
      (node (ref "R21") (pin "2") (pinfunction "2_2") (pintype "passive"))
    )
    (net (code "46") (name "Net-(IC2-(PCINT24{slash}RXD0)PD0)") (class "Default")
      (node (ref "IC2") (pin "9") (pinfunction "(PCINT24/RXD0)PD0_9") (pintype "bidirectional"))
      (node (ref "JP7") (pin "1") (pinfunction "1_1") (pintype "passive"))
    )
    (net (code "47") (name "Net-(IC2-(PCINT25{slash}TXD0)PD1)") (class "Default")
      (node (ref "IC2") (pin "10") (pinfunction "(PCINT25/TXD0)PD1_10") (pintype "bidirectional"))
      (node (ref "JP7") (pin "2") (pinfunction "2_2") (pintype "passive"))
    )
    (net (code "48") (name "Net-(IC2-AREF)") (class "Default")
      (node (ref "C4") (pin "1") (pinfunction "1_1") (pintype "passive"))
      (node (ref "IC2") (pin "29") (pinfunction "AREF_29") (pintype "passive"))
    )
    (net (code "49") (name "Net-(IC2-AVCC)") (class "Default")
      (node (ref "C10") (pin "2") (pinfunction "2_2") (pintype "passive"))
      (node (ref "IC2") (pin "17") (pinfunction "VCC_17") (pintype "power_in"))
      (node (ref "IC2") (pin "27") (pinfunction "AVCC_27") (pintype "power_in"))
      (node (ref "IC2") (pin "38") (pinfunction "VCC_38") (pintype "power_in"))
      (node (ref "IC2") (pin "5") (pinfunction "VCC_5") (pintype "power_in"))
      (node (ref "JP1") (pin "1") (pinfunction "1_1") (pintype "passive"))
      (node (ref "JP6") (pin "2") (pinfunction "2_2") (pintype "passive"))
    )
    (net (code "50") (name "Net-(IC2-RESET)") (class "Default")
      (node (ref "IC2") (pin "4") (pinfunction "RESET_4") (pintype "input"))
      (node (ref "JP6") (pin "5") (pinfunction "5_5") (pintype "passive"))
    )
    (net (code "51") (name "Net-(IC2-XTAL1)") (class "Default")
      (node (ref "C3") (pin "2") (pinfunction "2_2") (pintype "passive"))
      (node (ref "IC2") (pin "8") (pinfunction "XTAL1_8") (pintype "bidirectional"))
      (node (ref "Q1") (pin "1") (pinfunction "1_1") (pintype "passive"))
    )
    (net (code "52") (name "Net-(IC2-XTAL2)") (class "Default")
      (node (ref "C5") (pin "2") (pinfunction "2_2") (pintype "passive"))
      (node (ref "IC2") (pin "7") (pinfunction "XTAL2_7") (pintype "bidirectional"))
      (node (ref "Q1") (pin "2") (pinfunction "2_2") (pintype "passive"))
    )
    (net (code "53") (name "Net-(JP12-Pad2)") (class "Default")
      (node (ref "JP12") (pin "2") (pinfunction "2_2") (pintype "passive"))
      (node (ref "R23") (pin "1") (pinfunction "1_1") (pintype "passive"))
    )
    (net (code "54") (name "Net-(JP12-Pad3)") (class "Default")
      (node (ref "JP12") (pin "3") (pinfunction "3_3") (pintype "passive"))
      (node (ref "R22") (pin "1") (pinfunction "1_1") (pintype "passive"))
    )
    (net (code "55") (name "Net-(JP13-Pad2)") (class "Default")
      (node (ref "JP13") (pin "2") (pinfunction "2_2") (pintype "passive"))
      (node (ref "R25") (pin "1") (pinfunction "1_1") (pintype "passive"))
    )
    (net (code "56") (name "Net-(JP13-Pad3)") (class "Default")
      (node (ref "JP13") (pin "3") (pinfunction "3_3") (pintype "passive"))
      (node (ref "R24") (pin "1") (pinfunction "1_1") (pintype "passive"))
    )
    (net (code "57") (name "Net-(JP15-Pad2)") (class "Default")
      (node (ref "JP15") (pin "2") (pinfunction "2_2") (pintype "passive"))
      (node (ref "R27") (pin "1") (pinfunction "1_1") (pintype "passive"))
    )
    (net (code "58") (name "Net-(JP15-Pad3)") (class "Default")
      (node (ref "JP15") (pin "3") (pinfunction "3_3") (pintype "passive"))
      (node (ref "R26") (pin "1") (pinfunction "1_1") (pintype "passive"))
    )
    (net (code "59") (name "Net-(K2A-PA)") (class "Default")
      (node (ref "C13") (pin "1") (pinfunction "1_1") (pintype "passive"))
      (node (ref "K2") (pin "11@1") (pinfunction "PA_11@1") (pintype "passive"))
      (node (ref "K2") (pin "11@2") (pinfunction "PB_11@2") (pintype "passive"))
      (node (ref "X1") (pin "L2") (pinfunction "P2_L2") (pintype "bidirectional"))
    )
    (net (code "60") (name "Net-(K2A-SA)") (class "Default")
      (node (ref "K2") (pin "14@1") (pinfunction "SA_14@1") (pintype "passive"))
      (node (ref "K2") (pin "14@2") (pinfunction "SB_14@2") (pintype "passive"))
      (node (ref "X1") (pin "L4") (pinfunction "P4_L4") (pintype "bidirectional"))
      (node (ref "X2") (pin "L2") (pinfunction "P2_L2") (pintype "bidirectional"))
    )
    (net (code "61") (name "Net-(K2B-2)") (class "Default")
      (node (ref "D1") (pin "A") (pinfunction "A_A") (pintype "passive"))
      (node (ref "JP23") (pin "1") (pinfunction "1_1") (pintype "passive"))
      (node (ref "JP23") (pin "2") (pinfunction "2_2") (pintype "passive"))
      (node (ref "K2") (pin "A2") (pinfunction "2_A2") (pintype "passive"))
      (node (ref "T16") (pin "3") (pinfunction "D_3") (pintype "passive"))
    )
    (net (code "62") (name "Net-(LD1-C)") (class "Default")
      (node (ref "LD1") (pin "3") (pinfunction "C_3") (pintype "passive"))
      (node (ref "R21") (pin "1") (pinfunction "1_1") (pintype "passive"))
    )
    (net (code "63") (name "Net-(T1-B)") (class "Default")
      (node (ref "R4") (pin "1") (pinfunction "1_1") (pintype "passive"))
      (node (ref "T1") (pin "1") (pinfunction "B_1") (pintype "passive"))
    )
    (net (code "64") (name "Net-(T1-C)") (class "Default")
      (node (ref "R1") (pin "1") (pinfunction "1_1") (pintype "passive"))
      (node (ref "T1") (pin "3") (pinfunction "C_3") (pintype "passive"))
      (node (ref "T2") (pin "1") (pinfunction "G_1") (pintype "passive"))
    )
    (net (code "65") (name "Net-(T2-D)") (class "Default")
      (node (ref "C20") (pin "1") (pinfunction "1_1") (pintype "passive"))
      (node (ref "JP17") (pin "3") (pinfunction "3_3") (pintype "passive"))
      (node (ref "T2") (pin "3") (pinfunction "D_3") (pintype "passive"))
    )
    (net (code "66") (name "Net-(T3-B)") (class "Default")
      (node (ref "R5") (pin "1") (pinfunction "1_1") (pintype "passive"))
      (node (ref "T3") (pin "1") (pinfunction "B_1") (pintype "passive"))
    )
    (net (code "67") (name "Net-(T3-C)") (class "Default")
      (node (ref "R2") (pin "1") (pinfunction "1_1") (pintype "passive"))
      (node (ref "T3") (pin "3") (pinfunction "C_3") (pintype "passive"))
      (node (ref "T4") (pin "1") (pinfunction "G_1") (pintype "passive"))
    )
    (net (code "68") (name "Net-(T4-S)") (class "Default")
      (node (ref "C21") (pin "1") (pinfunction "1_1") (pintype "passive"))
      (node (ref "T4") (pin "2") (pinfunction "S_2") (pintype "passive"))
      (node (ref "X6") (pin "1") (pinfunction "1_1") (pintype "passive"))
    )
    (net (code "69") (name "Net-(T5-B)") (class "Default")
      (node (ref "R6") (pin "1") (pinfunction "1_1") (pintype "passive"))
      (node (ref "T5") (pin "1") (pinfunction "B_1") (pintype "passive"))
    )
    (net (code "70") (name "Net-(T5-C)") (class "Default")
      (node (ref "R3") (pin "1") (pinfunction "1_1") (pintype "passive"))
      (node (ref "T5") (pin "3") (pinfunction "C_3") (pintype "passive"))
      (node (ref "T6") (pin "1") (pinfunction "G_1") (pintype "passive"))
    )
    (net (code "71") (name "Net-(T6-D)") (class "Default")
      (node (ref "C22") (pin "1") (pinfunction "1_1") (pintype "passive"))
      (node (ref "JP18") (pin "3") (pinfunction "3_3") (pintype "passive"))
      (node (ref "R29") (pin "1") (pinfunction "1_1") (pintype "passive"))
      (node (ref "T6") (pin "3") (pinfunction "D_3") (pintype "passive"))
    )
    (net (code "72") (name "Net-(T7-B)") (class "Default")
      (node (ref "R7") (pin "1") (pinfunction "1_1") (pintype "passive"))
      (node (ref "T7") (pin "1") (pinfunction "B_1") (pintype "passive"))
    )
    (net (code "73") (name "Net-(T7-C)") (class "Default")
      (node (ref "R8") (pin "1") (pinfunction "1_1") (pintype "passive"))
      (node (ref "T7") (pin "3") (pinfunction "C_3") (pintype "passive"))
      (node (ref "T8") (pin "1") (pinfunction "G_1") (pintype "passive"))
    )
    (net (code "74") (name "Net-(T9-B)") (class "Default")
      (node (ref "R9") (pin "1") (pinfunction "1_1") (pintype "passive"))
      (node (ref "T9") (pin "1") (pinfunction "B_1") (pintype "passive"))
    )
    (net (code "75") (name "Net-(T10-D)") (class "Default")
      (node (ref "C26") (pin "1") (pinfunction "1_1") (pintype "passive"))
      (node (ref "D2") (pin "A") (pinfunction "A_A") (pintype "passive"))
      (node (ref "T10") (pin "3") (pinfunction "D_3") (pintype "passive"))
    )
    (net (code "76") (name "Net-(T10-G)") (class "Default")
      (node (ref "R10") (pin "1") (pinfunction "1_1") (pintype "passive"))
      (node (ref "T10") (pin "1") (pinfunction "G_1") (pintype "passive"))
      (node (ref "T9") (pin "3") (pinfunction "C_3") (pintype "passive"))
    )
    (net (code "77") (name "Net-(T11-B)") (class "Default")
      (node (ref "R11") (pin "1") (pinfunction "1_1") (pintype "passive"))
      (node (ref "T11") (pin "1") (pinfunction "B_1") (pintype "passive"))
    )
    (net (code "78") (name "Net-(T11-C)") (class "Default")
      (node (ref "R12") (pin "1") (pinfunction "1_1") (pintype "passive"))
      (node (ref "T11") (pin "3") (pinfunction "C_3") (pintype "passive"))
      (node (ref "T12") (pin "1") (pinfunction "G_1") (pintype "passive"))
    )
    (net (code "79") (name "Net-(T12-S)") (class "Default")
      (node (ref "C27") (pin "1") (pinfunction "1_1") (pintype "passive"))
      (node (ref "T12") (pin "2") (pinfunction "S_2") (pintype "passive"))
      (node (ref "X7") (pin "1") (pinfunction "1_1") (pintype "passive"))
    )
    (net (code "80") (name "Net-(T13-B)") (class "Default")
      (node (ref "R13") (pin "1") (pinfunction "1_1") (pintype "passive"))
      (node (ref "T13") (pin "1") (pinfunction "B_1") (pintype "passive"))
    )
    (net (code "81") (name "Net-(T13-C)") (class "Default")
      (node (ref "R14") (pin "1") (pinfunction "1_1") (pintype "passive"))
      (node (ref "T13") (pin "3") (pinfunction "C_3") (pintype "passive"))
      (node (ref "T14") (pin "1") (pinfunction "G_1") (pintype "passive"))
    )
    (net (code "82") (name "Net-(T14-S)") (class "Default")
      (node (ref "C28") (pin "1") (pinfunction "1_1") (pintype "passive"))
      (node (ref "T14") (pin "2") (pinfunction "S_2") (pintype "passive"))
      (node (ref "X8") (pin "1") (pinfunction "1_1") (pintype "passive"))
    )
    (net (code "83") (name "Net-(T15-B)") (class "Default")
      (node (ref "R15") (pin "1") (pinfunction "1_1") (pintype "passive"))
      (node (ref "T15") (pin "1") (pinfunction "B_1") (pintype "passive"))
    )
    (net (code "84") (name "Net-(T15-C)") (class "Default")
      (node (ref "JP16") (pin "3") (pinfunction "3_3") (pintype "passive"))
      (node (ref "T15") (pin "3") (pinfunction "C_3") (pintype "passive"))
    )
    (net (code "85") (name "Net-(T17-B)") (class "Default")
      (node (ref "R16") (pin "1") (pinfunction "1_1") (pintype "passive"))
      (node (ref "T17") (pin "1") (pinfunction "B_1") (pintype "passive"))
    )
    (net (code "86") (name "Net-(T17-C)") (class "Default")
      (node (ref "R17") (pin "1") (pinfunction "1_1") (pintype "passive"))
      (node (ref "T17") (pin "3") (pinfunction "C_3") (pintype "passive"))
      (node (ref "T18") (pin "1") (pinfunction "G_1") (pintype "passive"))
    )
    (net (code "87") (name "Net-(T19-B)") (class "Default")
      (node (ref "R18") (pin "2") (pinfunction "2_2") (pintype "passive"))
      (node (ref "T19") (pin "1") (pinfunction "B_1") (pintype "passive"))
    )
    (net (code "88") (name "Net-(T19-C)") (class "Default")
      (node (ref "R19") (pin "1") (pinfunction "1_1") (pintype "passive"))
      (node (ref "T19") (pin "3") (pinfunction "C_3") (pintype "passive"))
      (node (ref "T20") (pin "1") (pinfunction "G_1") (pintype "passive"))
    )
    (net (code "89") (name "Net-(T21-B)") (class "Default")
      (node (ref "R28") (pin "2") (pinfunction "2_2") (pintype "passive"))
      (node (ref "R29") (pin "2") (pinfunction "2_2") (pintype "passive"))
      (node (ref "T21") (pin "1") (pinfunction "B_1") (pintype "passive"))
    )
    (net (code "90") (name "Net-(T21-C)") (class "Default")
      (node (ref "JP18") (pin "2") (pinfunction "2_2") (pintype "passive"))
      (node (ref "T21") (pin "3") (pinfunction "C_3") (pintype "passive"))
    )
    (net (code "91") (name "VDD") (class "Default")
      (node (ref "C18") (pin "+") (pinfunction "+_+") (pintype "passive"))
      (node (ref "C19") (pin "1") (pinfunction "1_1") (pintype "passive"))
      (node (ref "C23") (pin "1") (pinfunction "1_1") (pintype "passive"))
      (node (ref "C24") (pin "1") (pinfunction "1_1") (pintype "passive"))
      (node (ref "C8") (pin "2") (pinfunction "2_2") (pintype "passive"))
      (node (ref "IC1") (pin "16") (pinfunction "VCC_16") (pintype "power_in"))
      (node (ref "JP1") (pin "2") (pinfunction "2_2") (pintype "passive"))
      (node (ref "JP10") (pin "3") (pinfunction "3_3") (pintype "passive"))
      (node (ref "JP19") (pin "3") (pinfunction "3_3") (pintype "passive"))
      (node (ref "LD1") (pin "1") (pinfunction "A_1") (pintype "passive"))
      (node (ref "LSP7") (pin "MP") (pinfunction "MP_MP") (pintype "passive"))
      (node (ref "R20") (pin "1") (pinfunction "1_1") (pintype "passive"))
      (node (ref "T12") (pin "3") (pinfunction "D_3") (pintype "passive"))
      (node (ref "T14") (pin "3") (pinfunction "D_3") (pintype "passive"))
      (node (ref "T4") (pin "3") (pinfunction "D_3") (pintype "passive"))
      (node (ref "X5") (pin "1") (pinfunction "1_1") (pintype "passive"))
    )
    (net (code "92") (name "unconnected-(DC1--VOUT-Pad4)") (class "Default")
      (node (ref "DC1") (pin "4") (pinfunction "-VOUT_4") (pintype "passive"))
    )
    (net (code "93") (name "unconnected-(DC2-+VIN-Pad2)") (class "Default")
      (node (ref "DC2") (pin "2") (pinfunction "+VIN_2") (pintype "passive"))
    )
    (net (code "94") (name "unconnected-(DC2-+VOUT-Pad4)") (class "Default")
      (node (ref "DC2") (pin "4") (pinfunction "+VOUT_4") (pintype "passive"))
    )
    (net (code "95") (name "unconnected-(DC2--VIN-Pad1)") (class "Default")
      (node (ref "DC2") (pin "1") (pinfunction "-VIN_1") (pintype "passive"))
    )
    (net (code "96") (name "unconnected-(DC2--VOUT-Pad3)") (class "Default")
      (node (ref "DC2") (pin "3") (pinfunction "-VOUT_3") (pintype "passive"))
    )
    (net (code "97") (name "unconnected-(IC1A-R2OUT-Pad9)") (class "Default")
      (node (ref "IC1") (pin "9") (pinfunction "R2OUT_9") (pintype "output"))
    )
    (net (code "98") (name "unconnected-(IC1A-T2OUT-Pad7)") (class "Default")
      (node (ref "IC1") (pin "7") (pinfunction "T2OUT_7") (pintype "output"))
    )
    (net (code "99") (name "unconnected-(IC2-(PCINT28{slash}OC1B)PD4-Pad13)") (class "Default")
      (node (ref "IC2") (pin "13") (pinfunction "(PCINT28/OC1B)PD4_13") (pintype "bidirectional"))
    )
    (net (code "100") (name "unconnected-(JP7-Pad4)") (class "Default")
      (node (ref "JP7") (pin "4") (pinfunction "4_4") (pintype "passive"))
    )
    (net (code "101") (name "unconnected-(LSP1-PadMP)") (class "Default")
      (node (ref "LSP1") (pin "MP") (pinfunction "MP_MP") (pintype "passive"))
    )
    (net (code "102") (name "unconnected-(LSP9-PadMP)") (class "Default")
      (node (ref "LSP9") (pin "MP") (pinfunction "MP_MP") (pintype "passive"))
    )
    (net (code "103") (name "unconnected-(X5-Pad2)") (class "Default")
      (node (ref "X5") (pin "2") (pinfunction "2_2") (pintype "passive"))
    )
    (net (code "104") (name "unconnected-(X5-Pad3)") (class "Default")
      (node (ref "X5") (pin "3") (pinfunction "3_3") (pintype "passive"))
    )
    (net (code "105") (name "unconnected-(X6-Pad2)") (class "Default")
      (node (ref "X6") (pin "2") (pinfunction "2_2") (pintype "passive"))
    )
    (net (code "106") (name "unconnected-(X6-Pad3)") (class "Default")
      (node (ref "X6") (pin "3") (pinfunction "3_3") (pintype "passive"))
    )
    (net (code "107") (name "unconnected-(X7-Pad2)") (class "Default")
      (node (ref "X7") (pin "2") (pinfunction "2_2") (pintype "passive"))
    )
    (net (code "108") (name "unconnected-(X7-Pad3)") (class "Default")
      (node (ref "X7") (pin "3") (pinfunction "3_3") (pintype "passive"))
    )
    (net (code "109") (name "unconnected-(X8-Pad2)") (class "Default")
      (node (ref "X8") (pin "2") (pinfunction "2_2") (pintype "passive"))
    )
    (net (code "110") (name "unconnected-(X8-Pad3)") (class "Default")
      (node (ref "X8") (pin "3") (pinfunction "3_3") (pintype "passive"))
    )
  )
)
